# PocketLEDs.net
KiCad netlist of a schematic drawn in EAGLE
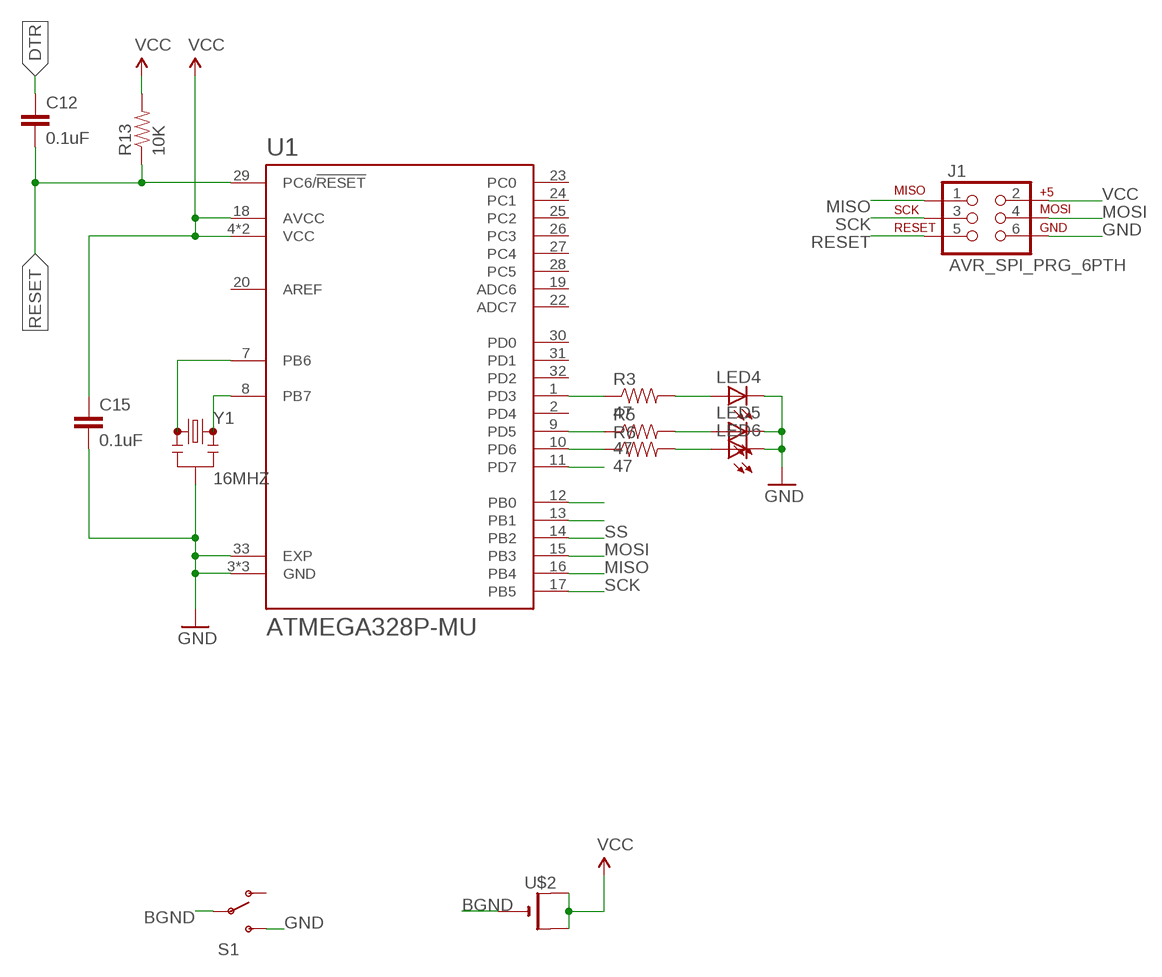
[diagram p0: schematic, sheet 1]

(export (version "E")
  (design (tool "Eeschema 10.0.6"))
  (components
    (comp (ref "C12")
      (value "0.1uF")
      (footprint "eagle-import:0805")
      (libsource (lib "eagle-import") (part "CAP0805"))
    )
    (comp (ref "C15")
      (value "0.1uF")
      (footprint "eagle-import:0805")
      (libsource (lib "eagle-import") (part "CAP0805"))
    )
    (comp (ref "J1")
      (value "AVR_SPI_PRG_6PTH")
      (footprint "eagle-import:2X3")
      (libsource (lib "eagle-import") (part "AVR_SPI_PRG_6PTH"))
    )
    (comp (ref "LED4")
      (value "LEDCHIPLED_0805")
      (footprint "eagle-import:CHIPLED_0805")
      (libsource (lib "eagle-import") (part "LEDCHIPLED_0805"))
    )
    (comp (ref "LED5")
      (value "LEDCHIPLED_0805")
      (footprint "eagle-import:CHIPLED_0805")
      (libsource (lib "eagle-import") (part "LEDCHIPLED_0805"))
    )
    (comp (ref "LED6")
      (value "LEDCHIPLED_0805")
      (footprint "eagle-import:CHIPLED_0805")
      (libsource (lib "eagle-import") (part "LEDCHIPLED_0805"))
    )
    (comp (ref "R3")
      (value "47")
      (footprint "eagle-import:0805")
      (libsource (lib "eagle-import") (part "SparkFun-Resistors_RESISTOR0805-RES"))
    )
    (comp (ref "R5")
      (value "47")
      (footprint "eagle-import:0805")
      (libsource (lib "eagle-import") (part "SparkFun-Resistors_RESISTOR0805-RES"))
    )
    (comp (ref "R6")
      (value "47")
      (footprint "eagle-import:0805")
      (libsource (lib "eagle-import") (part "SparkFun-Resistors_RESISTOR0805-RES"))
    )
    (comp (ref "R13")
      (value "10K")
      (footprint "eagle-import:0805")
      (libsource (lib "eagle-import") (part "RESISTOR0805-RES"))
    )
    (comp (ref "S1")
      (value "SWITCH-SPDT-SMD-A")
      (footprint "eagle-import:SWITCH-SPST-SMD-A")
      (libsource (lib "eagle-import") (part "SWITCH-SPDT-SMD-A"))
    )
    (comp (ref "U$2")
      (value "CR2032THM")
      (footprint "eagle-import:CR2032-THRU")
      (libsource (lib "eagle-import") (part "CR2032THM"))
    )
    (comp (ref "U1")
      (value "ATMEGA328P-MU")
      (footprint "eagle-import:QFN50P500X500X100-33N")
      (fields (field (name "MF") "Atmel"))
      (libsource (lib "eagle-import") (part "ATMEGA328P-MU"))
    )
    (comp (ref "Y1")
      (value "16MHZ")
      (footprint "eagle-import:RESONATOR-SMD")
      (libsource (lib "eagle-import") (part "RESONATOR16MHZ"))
    )
  )
  (nets
    (net (code "1") (name "/BGND") (class "Default")
      (node (ref "S1") (pin "2") (pinfunction "P_2") (pintype "passive"))
      (node (ref "U$2") (pin "-") (pinfunction "-_-") (pintype "passive"))
    )
    (net (code "2") (name "/MISO") (class "Default")
      (node (ref "J1") (pin "1") (pinfunction "1_1") (pintype "passive"))
      (node (ref "U1") (pin "16") (pinfunction "PB4_16") (pintype "bidirectional"))
    )
    (net (code "3") (name "/MOSI") (class "Default")
      (node (ref "J1") (pin "4") (pinfunction "4_4") (pintype "passive"))
      (node (ref "U1") (pin "15") (pinfunction "PB3_15") (pintype "bidirectional"))
    )
    (net (code "4") (name "/SCK") (class "Default")
      (node (ref "J1") (pin "3") (pinfunction "3_3") (pintype "passive"))
      (node (ref "U1") (pin "17") (pinfunction "PB5_17") (pintype "bidirectional"))
    )
    (net (code "5") (name "/SS") (class "Default")
      (node (ref "U1") (pin "14") (pinfunction "PB2_14") (pintype "bidirectional"))
    )
    (net (code "6") (name "DTR") (class "Default")
      (node (ref "C12") (pin "1") (pinfunction "1_1") (pintype "passive"))
    )
    (net (code "7") (name "GND") (class "Default")
      (node (ref "C15") (pin "2") (pinfunction "2_2") (pintype "passive"))
      (node (ref "J1") (pin "6") (pinfunction "6_6") (pintype "passive"))
      (node (ref "LED4") (pin "C") (pinfunction "C_C") (pintype "passive"))
      (node (ref "LED5") (pin "C") (pinfunction "C_C") (pintype "passive"))
      (node (ref "LED6") (pin "C") (pinfunction "C_C") (pintype "passive"))
      (node (ref "S1") (pin "3") (pinfunction "S_3") (pintype "passive"))
      (node (ref "U1") (pin "21") (pinfunction "GND_21") (pintype "power_in"))
      (node (ref "U1") (pin "3") (pinfunction "GND_3") (pintype "power_in"))
      (node (ref "U1") (pin "33") (pinfunction "EXP_33") (pintype "power_in"))
      (node (ref "U1") (pin "5") (pinfunction "GND_5") (pintype "power_in"))
      (node (ref "Y1") (pin "2") (pinfunction "2_2") (pintype "passive"))
    )
    (net (code "8") (name "Net-(LED4-PadA)") (class "Default")
      (node (ref "LED4") (pin "A") (pinfunction "A_A") (pintype "passive"))
      (node (ref "R3") (pin "2") (pinfunction "2_2") (pintype "passive"))
    )
    (net (code "9") (name "Net-(LED5-PadA)") (class "Default")
      (node (ref "LED5") (pin "A") (pinfunction "A_A") (pintype "passive"))
      (node (ref "R5") (pin "2") (pinfunction "2_2") (pintype "passive"))
    )
    (net (code "10") (name "Net-(LED6-PadA)") (class "Default")
      (node (ref "LED6") (pin "A") (pinfunction "A_A") (pintype "passive"))
      (node (ref "R6") (pin "2") (pinfunction "2_2") (pintype "passive"))
    )
    (net (code "11") (name "Net-(U1-PB6)") (class "Default")
      (node (ref "U1") (pin "7") (pinfunction "PB6_7") (pintype "bidirectional"))
      (node (ref "Y1") (pin "1") (pinfunction "1_1") (pintype "passive"))
    )
    (net (code "12") (name "Net-(U1-PB7)") (class "Default")
      (node (ref "U1") (pin "8") (pinfunction "PB7_8") (pintype "bidirectional"))
      (node (ref "Y1") (pin "3") (pinfunction "3_3") (pintype "passive"))
    )
    (net (code "13") (name "Net-(U1-PD3)") (class "Default")
      (node (ref "R3") (pin "1") (pinfunction "1_1") (pintype "passive"))
      (node (ref "U1") (pin "1") (pinfunction "PD3_1") (pintype "bidirectional"))
    )
    (net (code "14") (name "Net-(U1-PD5)") (class "Default")
      (node (ref "R5") (pin "1") (pinfunction "1_1") (pintype "passive"))
      (node (ref "U1") (pin "9") (pinfunction "PD5_9") (pintype "bidirectional"))
    )
    (net (code "15") (name "Net-(U1-PD6)") (class "Default")
      (node (ref "R6") (pin "1") (pinfunction "1_1") (pintype "passive"))
      (node (ref "U1") (pin "10") (pinfunction "PD6_10") (pintype "bidirectional"))
    )
    (net (code "16") (name "RESET") (class "Default")
      (node (ref "C12") (pin "2") (pinfunction "2_2") (pintype "passive"))
      (node (ref "J1") (pin "5") (pinfunction "5_5") (pintype "passive"))
      (node (ref "R13") (pin "1") (pinfunction "1_1") (pintype "passive"))
      (node (ref "U1") (pin "29") (pinfunction "PC6/~{RESET}_29") (pintype "bidirectional"))
    )
    (net (code "17") (name "VCC") (class "Default")
      (node (ref "C15") (pin "1") (pinfunction "1_1") (pintype "passive"))
      (node (ref "J1") (pin "2") (pinfunction "2_2") (pintype "passive"))
      (node (ref "R13") (pin "2") (pinfunction "2_2") (pintype "passive"))
      (node (ref "U$2") (pin "+1") (pinfunction "+_+1") (pintype "passive"))
      (node (ref "U$2") (pin "+2") (pinfunction "+1_+2") (pintype "passive"))
      (node (ref "U1") (pin "18") (pinfunction "AVCC_18") (pintype "power_in"))
      (node (ref "U1") (pin "4") (pinfunction "VCC_4") (pintype "power_in"))
      (node (ref "U1") (pin "6") (pinfunction "VCC_6") (pintype "power_in"))
    )
    (net (code "18") (name "unconnected-(S1-O-Pad1)") (class "Default")
      (node (ref "S1") (pin "1") (pinfunction "O_1") (pintype "passive"))
    )
    (net (code "19") (name "unconnected-(U1-ADC6-Pad19)") (class "Default")
      (node (ref "U1") (pin "19") (pinfunction "ADC6_19") (pintype "bidirectional"))
    )
    (net (code "20") (name "unconnected-(U1-ADC7-Pad22)") (class "Default")
      (node (ref "U1") (pin "22") (pinfunction "ADC7_22") (pintype "bidirectional"))
    )
    (net (code "21") (name "unconnected-(U1-AREF-Pad20)") (class "Default")
      (node (ref "U1") (pin "20") (pinfunction "AREF_20") (pintype "input"))
    )
    (net (code "22") (name "unconnected-(U1-PB0-Pad12)") (class "Default")
      (node (ref "U1") (pin "12") (pinfunction "PB0_12") (pintype "bidirectional"))
    )
    (net (code "23") (name "unconnected-(U1-PB1-Pad13)") (class "Default")
      (node (ref "U1") (pin "13") (pinfunction "PB1_13") (pintype "bidirectional"))
    )
    (net (code "24") (name "unconnected-(U1-PC0-Pad23)") (class "Default")
      (node (ref "U1") (pin "23") (pinfunction "PC0_23") (pintype "bidirectional"))
    )
    (net (code "25") (name "unconnected-(U1-PC1-Pad24)") (class "Default")
      (node (ref "U1") (pin "24") (pinfunction "PC1_24") (pintype "bidirectional"))
    )
    (net (code "26") (name "unconnected-(U1-PC2-Pad25)") (class "Default")
      (node (ref "U1") (pin "25") (pinfunction "PC2_25") (pintype "bidirectional"))
    )
    (net (code "27") (name "unconnected-(U1-PC3-Pad26)") (class "Default")
      (node (ref "U1") (pin "26") (pinfunction "PC3_26") (pintype "bidirectional"))
    )
    (net (code "28") (name "unconnected-(U1-PC4-Pad27)") (class "Default")
      (node (ref "U1") (pin "27") (pinfunction "PC4_27") (pintype "bidirectional"))
    )
    (net (code "29") (name "unconnected-(U1-PC5-Pad28)") (class "Default")
      (node (ref "U1") (pin "28") (pinfunction "PC5_28") (pintype "bidirectional"))
    )
    (net (code "30") (name "unconnected-(U1-PD0-Pad30)") (class "Default")
      (node (ref "U1") (pin "30") (pinfunction "PD0_30") (pintype "bidirectional"))
    )
    (net (code "31") (name "unconnected-(U1-PD1-Pad31)") (class "Default")
      (node (ref "U1") (pin "31") (pinfunction "PD1_31") (pintype "bidirectional"))
    )
    (net (code "32") (name "unconnected-(U1-PD2-Pad32)") (class "Default")
      (node (ref "U1") (pin "32") (pinfunction "PD2_32") (pintype "bidirectional"))
    )
    (net (code "33") (name "unconnected-(U1-PD4-Pad2)") (class "Default")
      (node (ref "U1") (pin "2") (pinfunction "PD4_2") (pintype "bidirectional"))
    )
    (net (code "34") (name "unconnected-(U1-PD7-Pad11)") (class "Default")
      (node (ref "U1") (pin "11") (pinfunction "PD7_11") (pintype "bidirectional"))
    )
  )
)
